# SensWear_Power.net
KiCad netlist of a schematic drawn in Altium Designer
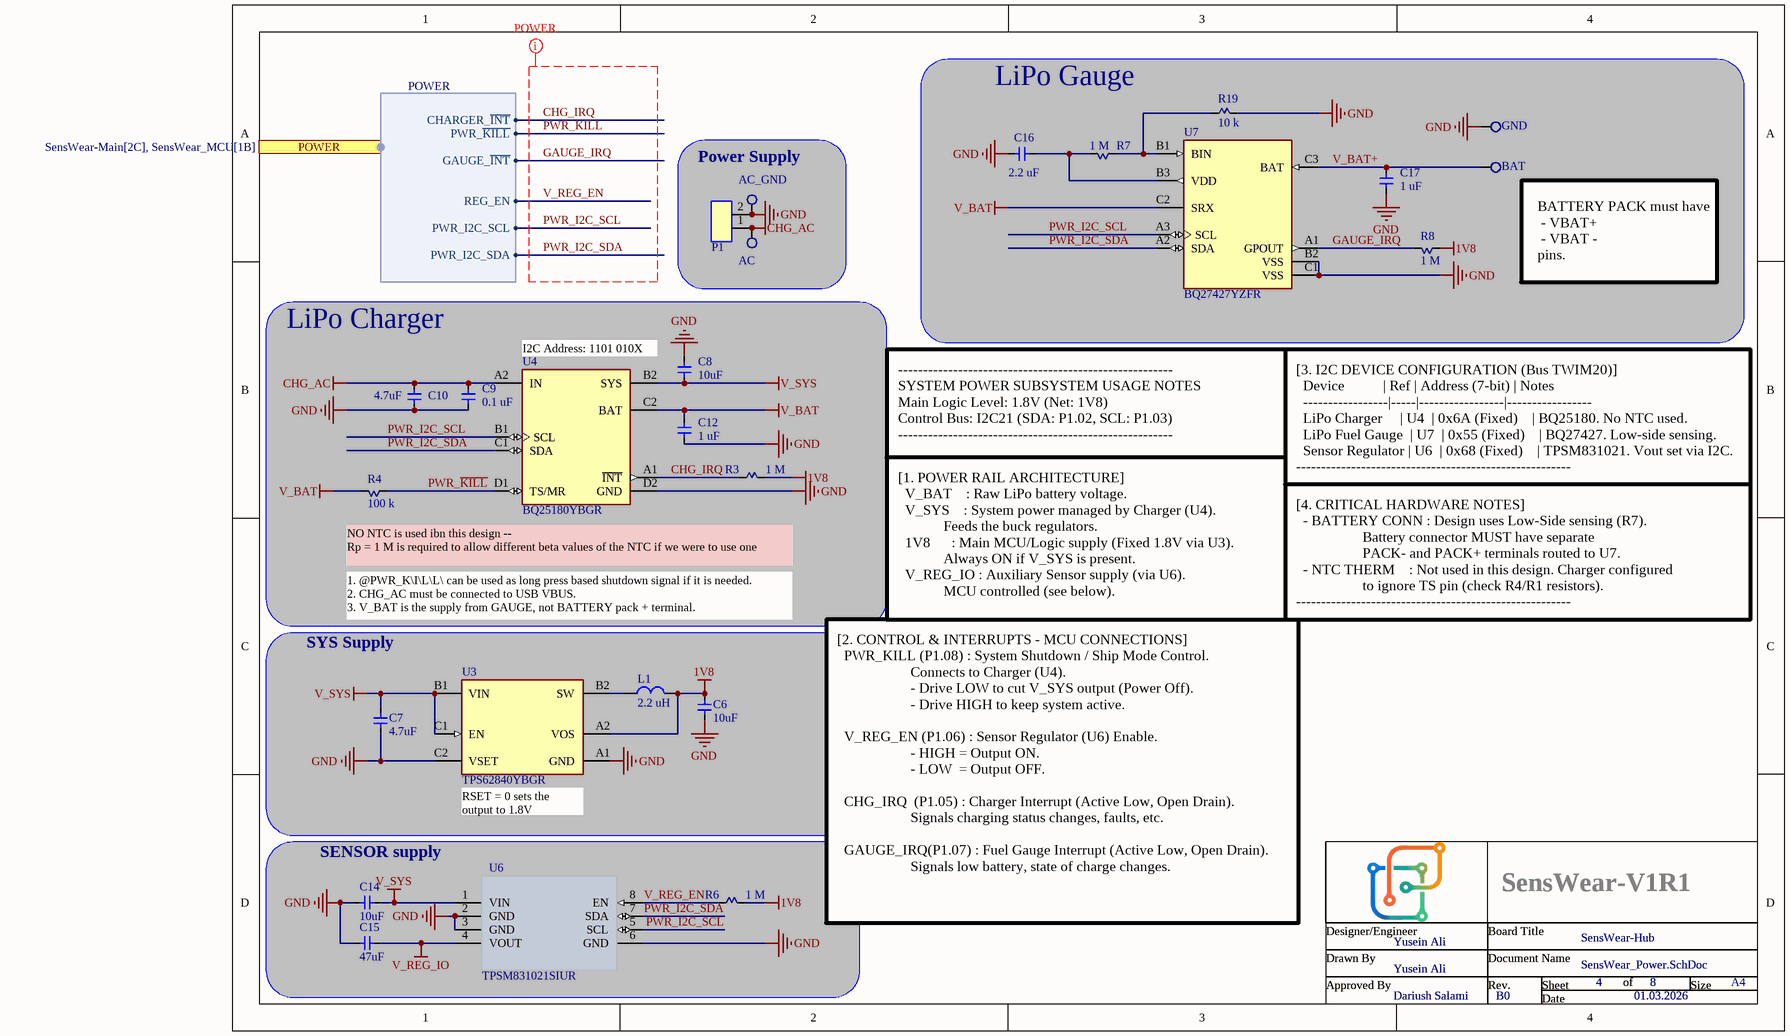
[diagram p0: SensWear_Power.SchDoc]

(export (version "E")
  (design (tool "Eeschema 10.0.6"))
  (components
    (comp (ref "AC")
      (value "TESTPAD")
      (footprint "TEST_PAD")
      (description "TESTPOINT PIN SMD")
      (libsource (lib "SensWearComponents") (part "TESTPAD"))
    )
    (comp (ref "AC_GND")
      (value "TESTPAD")
      (footprint "TEST_PAD")
      (description "TESTPOINT PIN SMD")
      (libsource (lib "SensWearComponents") (part "TESTPAD"))
    )
    (comp (ref "BAT")
      (value "TESTPAD")
      (footprint "TEST_PAD")
      (description "TESTPOINT PIN SMD")
      (libsource (lib "SensWearComponents") (part "TESTPAD"))
    )
    (comp (ref "C6")
      (value "10uF")
      (footprint "CAPC1005X05N")
      (description "Multilayer Ceramic Capacitor, 10 uF, 10 V, ± 20%, X5R, 0402 [1005 Metric]")
      (fields
        (field (name "MANUFACTURER") "Samsung")
        (field (name "MANUFACTURER PART NUMBER") "CL05A106MP5NUNC")
      )
      (libsource (lib "SensWearComponents") (part "CL05A106MP5NUNC"))
    )
    (comp (ref "C7")
      (value "4.7uF")
      (footprint "CAPC1005X05N")
      (description "Multilayer Ceramic Capacitor, 4.7 uF, 10 V, ± 20%, X5R, 0402 [1005 Metric]")
      (fields
        (field (name "MANUFACTURER") "Murata")
        (field (name "MANUFACTURER PART NUMBER") "GRM155R61A475MEAAD")
      )
      (libsource (lib "SensWearComponents") (part "GRM155R61A475MEAAD__2"))
    )
    (comp (ref "C8")
      (value "10uF")
      (footprint "CAPC1005X05N")
      (description "Multilayer Ceramic Capacitor, 10 uF, 10 V, ± 20%, X5R, 0402 [1005 Metric]")
      (fields
        (field (name "MANUFACTURER") "Samsung")
        (field (name "MANUFACTURER PART NUMBER") "CL05A106MP5NUNC")
      )
      (libsource (lib "SensWearComponents") (part "CL05A106MP5NUNC"))
    )
    (comp (ref "C9")
      (value "0.1 uF")
      (footprint "CAPC1005X05N")
      (description "CAP CER 0.1UF 16V X5R 0402")
      (fields
        (field (name "MANUFACTURER") "Murata Electronics")
        (field (name "MANUFACTURER PART NUMBER") "GRM155R61C104KA88D")
      )
      (libsource (lib "SensWearComponents") (part "GRM155R61C104KA88D__2"))
    )
    (comp (ref "C10")
      (value "4.7uF")
      (footprint "CAPC1005X05N")
      (description "Multilayer Ceramic Capacitor, 4.7 uF, 10 V, ± 20%, X5R, 0402 [1005 Metric]")
      (fields
        (field (name "MANUFACTURER") "Murata")
        (field (name "MANUFACTURER PART NUMBER") "GRM155R61A475MEAAD")
      )
      (libsource (lib "SensWearComponents") (part "GRM155R61A475MEAAD__2"))
    )
    (comp (ref "C12")
      (value "1 uF")
      (footprint "CAPC1005X05N")
      (description "CAP CER 1UF 10V X5R 0402")
      (fields
        (field (name "MANUFACTURER") "Murata Electronics North America")
        (field (name "MANUFACTURER PART NUMBER") "GRM155R61A105KE15D")
      )
      (libsource (lib "SensWearComponents") (part "GRM155R61A105KE15D__2"))
    )
    (comp (ref "C14")
      (value "10uF")
      (footprint "CAPC1005X05N")
      (description "Multilayer Ceramic Capacitor, 10 uF, 10 V, ± 20%, X5R, 0402 [1005 Metric]")
      (fields
        (field (name "MANUFACTURER") "Samsung")
        (field (name "MANUFACTURER PART NUMBER") "CL05A106MP5NUNC")
      )
      (libsource (lib "SensWearComponents") (part "CL05A106MP5NUNC"))
    )
    (comp (ref "C15")
      (value "47uF")
      (footprint "CAPC1610X05N")
      (description "CL10 Series 0603 47 uF 6.3 V ±20% Tolerance X5R Multilayer Ceramic Capacitor")
      (fields
        (field (name "MANUFACTURER") "Samsung")
        (field (name "MANUFACTURER PART NUMBER") "CL10A476MQ8QRNC")
      )
      (libsource (lib "SensWearComponents") (part "CL10A476MQ8QRNC"))
    )
    (comp (ref "C16")
      (value "2.2 uF")
      (footprint "CAPC1005X05N")
      (description "CAP CER 2.2UF 10V X5R 0402")
      (fields
        (field (name "MANUFACTURER") "Murata Electronics North America")
        (field (name "MANUFACTURER PART NUMBER") "GRM155R61A225KE95D")
      )
      (libsource (lib "SensWearComponents") (part "GRM155R61A225KE95D"))
    )
    (comp (ref "C17")
      (value "1 uF")
      (footprint "CAPC1005X05N")
      (description "CAP CER 1UF 10V X5R 0402")
      (fields
        (field (name "MANUFACTURER") "Murata Electronics North America")
        (field (name "MANUFACTURER PART NUMBER") "GRM155R61A105KE15D")
      )
      (libsource (lib "SensWearComponents") (part "GRM155R61A105KE15D__2"))
    )
    (comp (ref "GND")
      (value "TESTPAD")
      (footprint "TEST_PAD")
      (description "TESTPOINT PIN SMD")
      (libsource (lib "SensWearComponents") (part "TESTPAD"))
    )
    (comp (ref "L1")
      (value "2.2 uH")
      (footprint "FP-DFE201612C-MFG")
      (description "Inductor Power Shielded Wirewound 2.2uH 20% 1MHz Metal 1.8A 0.116Ohm DCR 0806 T/R")
      (fields
        (field (name "MANUFACTURER") "Murata")
        (field (name "MANUFACTURER PART NUMBER") "DFE201612E-2R2M=P2")
      )
      (libsource (lib "SensWearComponents") (part "DFE201612E-2R2M=P2"))
    )
    (comp (ref "P1")
      (value "RM-1238-B02-41")
      (footprint "RM-1238-B02-41_2")
      (description "RM-1238-B02-41 by www.xtpogopin.com")
      (fields (field (name "MANUFACTURER") "XTPogoPin"))
      (libsource (lib "SensWearComponents") (part "RM-1238-B02-41"))
    )
    (comp (ref "R3")
      (value "1 M")
      (footprint "RESC1005X04N")
      (description "RES SMD 1M OHM 1% 1/10W 0402")
      (fields
        (field (name "MANUFACTURER") "Panasonic Electronic Components")
        (field (name "MANUFACTURER PART NUMBER") "ERJ-2RKF1004X")
      )
      (libsource (lib "SensWearComponents") (part "ERJ-2RKF1004X"))
    )
    (comp (ref "R4")
      (value "100 k")
      (footprint "RESC1005X04N")
      (description "RES SMD 100K OHM 1% 1/10W 0402")
      (fields
        (field (name "MANUFACTURER") "Panasonic Electronic Components")
        (field (name "MANUFACTURER PART NUMBER") "ERJ-2RKF1003X")
      )
      (libsource (lib "SensWearComponents") (part "ERJ-2RKF1003X"))
    )
    (comp (ref "R6")
      (value "1 M")
      (footprint "RESC1005X04N")
      (description "RES SMD 1M OHM 1% 1/10W 0402")
      (fields
        (field (name "MANUFACTURER") "Panasonic Electronic Components")
        (field (name "MANUFACTURER PART NUMBER") "ERJ-2RKF1004X")
      )
      (libsource (lib "SensWearComponents") (part "ERJ-2RKF1004X"))
    )
    (comp (ref "R7")
      (value "1 M")
      (footprint "RESC1005X04N")
      (description "RES SMD 1M OHM 1% 1/10W 0402")
      (fields
        (field (name "MANUFACTURER") "Panasonic Electronic Components")
        (field (name "MANUFACTURER PART NUMBER") "ERJ-2RKF1004X")
      )
      (libsource (lib "SensWearComponents") (part "ERJ-2RKF1004X"))
    )
    (comp (ref "R8")
      (value "1 M")
      (footprint "RESC1005X04N")
      (description "RES SMD 1M OHM 1% 1/10W 0402")
      (fields
        (field (name "MANUFACTURER") "Panasonic Electronic Components")
        (field (name "MANUFACTURER PART NUMBER") "ERJ-2RKF1004X")
      )
      (libsource (lib "SensWearComponents") (part "ERJ-2RKF1004X"))
    )
    (comp (ref "R19")
      (value "10 k")
      (footprint "RESC1005X04N")
      (description "RES SMD 10K OHM 1% 1/10W 0402")
      (fields
        (field (name "MANUFACTURER") "Panasonic Electronic Components")
        (field (name "MANUFACTURER PART NUMBER") "ERJ-2RKF1002X")
      )
      (libsource (lib "SensWearComponents") (part "ERJ-2RKF1002X__2"))
    )
    (comp (ref "U3")
      (value "TPS62840YBGR")
      (footprint "BGA6C40P2X3_97X147X50")
      (description "Conv DC-DC 1.8V to 6.5V Synchronous Step Down Single-Out 1.8V to 3.3V 0.75A 6-Pin DSBGA T/R")
      (fields (field (name "MANUFACTURER") "Texas Instruments"))
      (libsource (lib "SensWearComponents") (part "TPS62840YBGR"))
    )
    (comp (ref "U4")
      (value "BQ25180YBGR")
      (footprint "BGA8C40P2X4_104X159X50")
      (description "1-A Li-ion I²C programmable charger with regulated power path in WCSP package 8-DSBGA -40 to 85")
      (fields (field (name "MANUFACTURER") "Texas Instruments"))
      (libsource (lib "SensWearComponents") (part "BQ25180YBGR"))
    )
    (comp (ref "U6")
      (value "TPSM831021SIUR")
      (footprint "MicroSiP8_SIU-A_TEX-M")
      (fields (field (name "MANUFACTURER") "Texas Instruments"))
      (libsource (lib "SensWearComponents") (part "TPSM831021SIUR"))
    )
    (comp (ref "U7")
      (value "BQ27427YZFR")
      (footprint "BGA9C50P3X3_158X162X62")
      (fields (field (name "MANUFACTURER") "Texas Instruments"))
      (libsource (lib "SensWearComponents") (part "BQ27427YZFR"))
    )
  )
  (nets
    (net (code "2") (name "/CHG_IRQ") (class "Default")
      (node (ref "R3") (pin "2") (pinfunction "2_2") (pintype "passive"))
      (node (ref "U4") (pin "A1") (pinfunction "~{INT}_A1") (pintype "output"))
    )
    (net (code "3") (name "/GAUGE_IRQ") (class "Default")
      (node (ref "R8") (pin "2") (pinfunction "2_2") (pintype "passive"))
      (node (ref "U7") (pin "A1") (pinfunction "GPOUT_A1") (pintype "output"))
    )
    (net (code "4") (name "/PWR_I2C_SCL") (class "Default")
      (node (ref "U4") (pin "B1") (pinfunction "SCL_B1") (pintype "bidirectional"))
      (node (ref "U6") (pin "5") (pinfunction "SCL_5") (pintype "bidirectional"))
      (node (ref "U7") (pin "A3") (pinfunction "SCL_A3") (pintype "bidirectional"))
    )
    (net (code "5") (name "/PWR_I2C_SDA") (class "Default")
      (node (ref "U4") (pin "C1") (pinfunction "SDA_C1") (pintype "bidirectional"))
      (node (ref "U6") (pin "7") (pinfunction "SDA_7") (pintype "bidirectional"))
      (node (ref "U7") (pin "A2") (pinfunction "SDA_A2") (pintype "bidirectional"))
    )
    (net (code "6") (name "/PWR_~{KILL}") (class "Default")
      (node (ref "R4") (pin "1") (pinfunction "1_1") (pintype "passive"))
      (node (ref "U4") (pin "D1") (pinfunction "TS/MR_D1") (pintype "bidirectional"))
    )
    (net (code "7") (name "/V_BAT+") (class "Default")
      (node (ref "BAT") (pin "1") (pinfunction "1_1") (pintype "passive"))
      (node (ref "C17") (pin "1") (pinfunction "1_1") (pintype "passive"))
      (node (ref "U7") (pin "C3") (pinfunction "BAT_C3") (pintype "input"))
    )
    (net (code "8") (name "/V_REG_EN") (class "Default")
      (node (ref "R6") (pin "2") (pinfunction "2_2") (pintype "passive"))
      (node (ref "U6") (pin "8") (pinfunction "EN_8") (pintype "input"))
    )
    (net (code "10") (name "1V8") (class "Default")
      (node (ref "C6") (pin "1") (pinfunction "1_1") (pintype "passive"))
      (node (ref "L1") (pin "2") (pinfunction "2_2") (pintype "passive"))
      (node (ref "R3") (pin "1") (pinfunction "1_1") (pintype "passive"))
      (node (ref "R6") (pin "1") (pinfunction "1_1") (pintype "passive"))
      (node (ref "R8") (pin "1") (pinfunction "1_1") (pintype "passive"))
      (node (ref "U3") (pin "A2") (pinfunction "VOS_A2") (pintype "power_in"))
    )
    (net (code "11") (name "CHG_AC") (class "Default")
      (node (ref "AC") (pin "1") (pinfunction "1_1") (pintype "passive"))
      (node (ref "C10") (pin "2") (pinfunction "2_2") (pintype "passive"))
      (node (ref "C9") (pin "1") (pinfunction "1_1") (pintype "passive"))
      (node (ref "P1") (pin "1") (pinfunction "1_1") (pintype "passive"))
      (node (ref "U4") (pin "A2") (pinfunction "IN_A2") (pintype "power_in"))
    )
    (net (code "12") (name "GND") (class "Default")
      (node (ref "AC_GND") (pin "1") (pinfunction "1_1") (pintype "passive"))
      (node (ref "C10") (pin "1") (pinfunction "1_1") (pintype "passive"))
      (node (ref "C12") (pin "2") (pinfunction "2_2") (pintype "passive"))
      (node (ref "C14") (pin "1") (pinfunction "1_1") (pintype "passive"))
      (node (ref "C15") (pin "1") (pinfunction "1_1") (pintype "passive"))
      (node (ref "C16") (pin "2") (pinfunction "2_2") (pintype "passive"))
      (node (ref "C17") (pin "2") (pinfunction "2_2") (pintype "passive"))
      (node (ref "C6") (pin "2") (pinfunction "2_2") (pintype "passive"))
      (node (ref "C7") (pin "1") (pinfunction "1_1") (pintype "passive"))
      (node (ref "C8") (pin "2") (pinfunction "2_2") (pintype "passive"))
      (node (ref "C9") (pin "2") (pinfunction "2_2") (pintype "passive"))
      (node (ref "GND") (pin "1") (pinfunction "1_1") (pintype "passive"))
      (node (ref "P1") (pin "2") (pinfunction "2_2") (pintype "passive"))
      (node (ref "R19") (pin "2") (pinfunction "2_2") (pintype "passive"))
      (node (ref "U3") (pin "A1") (pinfunction "GND_A1") (pintype "power_in"))
      (node (ref "U3") (pin "C2") (pinfunction "VSET_C2") (pintype "power_in"))
      (node (ref "U4") (pin "D2") (pinfunction "GND_D2") (pintype "power_in"))
      (node (ref "U6") (pin "2") (pinfunction "GND_2") (pintype "power_in"))
      (node (ref "U6") (pin "3") (pinfunction "GND_3") (pintype "power_in"))
      (node (ref "U6") (pin "6") (pinfunction "GND_6") (pintype "power_in"))
      (node (ref "U7") (pin "B2") (pinfunction "VSS_B2") (pintype "power_in"))
      (node (ref "U7") (pin "C1") (pinfunction "VSS_C1") (pintype "power_in"))
    )
    (net (code "13") (name "Net-(U3-SW)") (class "Default")
      (node (ref "L1") (pin "1") (pinfunction "1_1") (pintype "passive"))
      (node (ref "U3") (pin "B2") (pinfunction "SW_B2") (pintype "power_in"))
    )
    (net (code "14") (name "Net-(U7-BIN)") (class "Default")
      (node (ref "R19") (pin "1") (pinfunction "1_1") (pintype "passive"))
      (node (ref "R7") (pin "1") (pinfunction "1_1") (pintype "passive"))
      (node (ref "U7") (pin "B1") (pinfunction "BIN_B1") (pintype "input"))
    )
    (net (code "15") (name "Net-(U7-VDD)") (class "Default")
      (node (ref "C16") (pin "1") (pinfunction "1_1") (pintype "passive"))
      (node (ref "R7") (pin "2") (pinfunction "2_2") (pintype "passive"))
      (node (ref "U7") (pin "B3") (pinfunction "VDD_B3") (pintype "output"))
    )
    (net (code "16") (name "V_BAT") (class "Default")
      (node (ref "C12") (pin "1") (pinfunction "1_1") (pintype "passive"))
      (node (ref "R4") (pin "2") (pinfunction "2_2") (pintype "passive"))
      (node (ref "U4") (pin "C2") (pinfunction "BAT_C2") (pintype "power_in"))
      (node (ref "U7") (pin "C2") (pinfunction "SRX_C2") (pintype "power_in"))
    )
    (net (code "17") (name "V_REG_IO") (class "Default")
      (node (ref "C15") (pin "2") (pinfunction "2_2") (pintype "passive"))
      (node (ref "U6") (pin "4") (pinfunction "VOUT_4") (pintype "power_in"))
    )
    (net (code "18") (name "V_SYS") (class "Default")
      (node (ref "C14") (pin "2") (pinfunction "2_2") (pintype "passive"))
      (node (ref "C7") (pin "2") (pinfunction "2_2") (pintype "passive"))
      (node (ref "C8") (pin "1") (pinfunction "1_1") (pintype "passive"))
      (node (ref "U3") (pin "B1") (pinfunction "VIN_B1") (pintype "power_in"))
      (node (ref "U3") (pin "C1") (pinfunction "EN_C1") (pintype "input"))
      (node (ref "U4") (pin "B2") (pinfunction "SYS_B2") (pintype "power_in"))
      (node (ref "U6") (pin "1") (pinfunction "VIN_1") (pintype "power_in"))
    )
  )
)
